# BlueSMiRF-ChipAnt.net
KiCad netlist of a schematic drawn in EAGLE
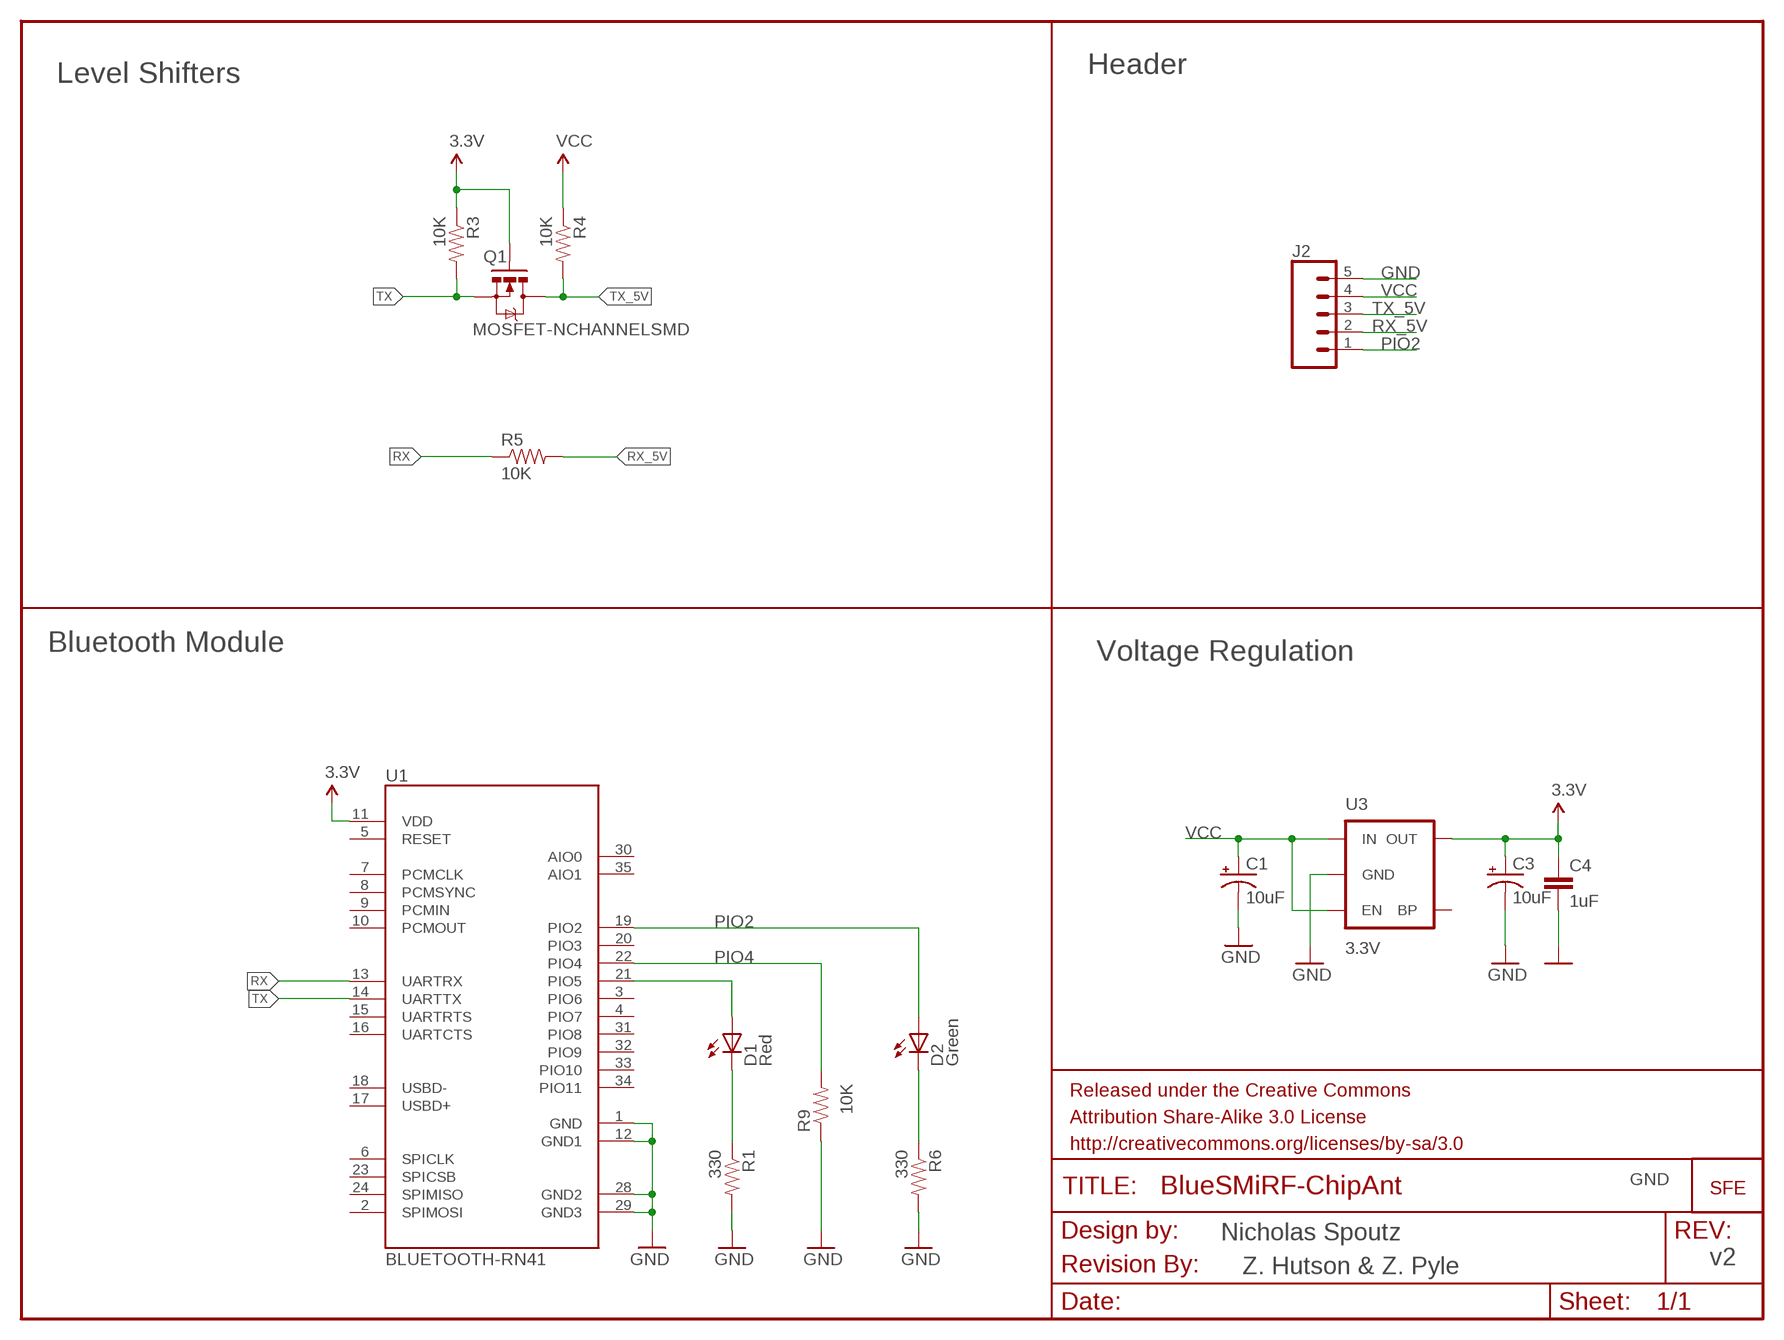
[diagram p0: schematic, sheet 1]

(export (version "E")
  (design (tool "Eeschema 10.0.6"))
  (components
    (comp (ref "C1")
      (value "10uF")
      (footprint "eagle-import:EIA3216")
      (libsource (lib "eagle-import") (part "CAP_POL1206"))
    )
    (comp (ref "C3")
      (value "10uF")
      (footprint "eagle-import:EIA3216")
      (libsource (lib "eagle-import") (part "CAP_POL1206"))
    )
    (comp (ref "C4")
      (value "1uF")
      (footprint "eagle-import:0603-CAP")
      (libsource (lib "eagle-import") (part "CAP0603-CAP"))
    )
    (comp (ref "D1")
      (value "Red")
      (footprint "eagle-import:LED-0603")
      (libsource (lib "eagle-import") (part "LED0603"))
    )
    (comp (ref "D2")
      (value "Green")
      (footprint "eagle-import:LED-0603")
      (libsource (lib "eagle-import") (part "LED0603"))
    )
    (comp (ref "FRAME1")
      (value "FRAME-LETTER")
      (footprint "eagle-import:CREATIVE_COMMONS")
      (libsource (lib "eagle-import") (part "FRAME-LETTER"))
    )
    (comp (ref "J2")
      (value "CONN_05JST")
      (footprint "eagle-import:JST-5-PTH")
      (libsource (lib "eagle-import") (part "CONN_05JST"))
    )
    (comp (ref "Q1")
      (value "MOSFET-NCHANNELSMD")
      (footprint "eagle-import:SOT23-3")
      (libsource (lib "eagle-import") (part "MOSFET-NCHANNELSMD"))
    )
    (comp (ref "R1")
      (value "330")
      (footprint "eagle-import:0603-RES")
      (libsource (lib "eagle-import") (part "RESISTOR0603-RES"))
    )
    (comp (ref "R3")
      (value "10K")
      (footprint "eagle-import:0603-RES")
      (libsource (lib "eagle-import") (part "RESISTOR0603-RES"))
    )
    (comp (ref "R4")
      (value "10K")
      (footprint "eagle-import:0603-RES")
      (libsource (lib "eagle-import") (part "RESISTOR0603-RES"))
    )
    (comp (ref "R5")
      (value "10K")
      (footprint "eagle-import:0603-RES")
      (libsource (lib "eagle-import") (part "RESISTOR0603-RES"))
    )
    (comp (ref "R6")
      (value "330")
      (footprint "eagle-import:0603-RES")
      (libsource (lib "eagle-import") (part "RESISTOR0603-RES"))
    )
    (comp (ref "R9")
      (value "10K")
      (footprint "eagle-import:0603-RES")
      (libsource (lib "eagle-import") (part "RESISTOR0603-RES"))
    )
    (comp (ref "U$1")
      (value "LOGO-SFENEW")
      (footprint "eagle-import:SFE-NEW-WEBLOGO")
      (libsource (lib "eagle-import") (part "LOGO-SFENEW"))
    )
    (comp (ref "U$2")
      (value "REVISION")
      (footprint "eagle-import:REVISION")
      (libsource (lib "eagle-import") (part "REVISION"))
    )
    (comp (ref "U1")
      (value "BLUETOOTH-RN41")
      (footprint "eagle-import:RN41")
      (libsource (lib "eagle-import") (part "BLUETOOTH-RN41{dblquote}"))
    )
    (comp (ref "U3")
      (value "3.3V")
      (footprint "eagle-import:SOT23-5")
      (libsource (lib "eagle-import") (part "V_REG_LDOSMD"))
    )
  )
  (nets
    (net (code "1") (name "/PIO2") (class "Default")
      (node (ref "D2") (pin "A") (pinfunction "A_A") (pintype "passive"))
      (node (ref "J2") (pin "1") (pinfunction "1_1") (pintype "passive"))
      (node (ref "U1") (pin "19") (pinfunction "PIO2_19") (pintype "bidirectional"))
    )
    (net (code "2") (name "/PIO4") (class "Default")
      (node (ref "R9") (pin "2") (pinfunction "2_2") (pintype "passive"))
      (node (ref "U1") (pin "22") (pinfunction "PIO4_22") (pintype "bidirectional"))
    )
    (net (code "3") (name "3.3V") (class "Default")
      (node (ref "C3") (pin "A") (pinfunction "+_A") (pintype "passive"))
      (node (ref "C4") (pin "1") (pinfunction "1_1") (pintype "passive"))
      (node (ref "Q1") (pin "1") (pinfunction "G_1") (pintype "passive"))
      (node (ref "R3") (pin "1") (pinfunction "1_1") (pintype "passive"))
      (node (ref "U1") (pin "11") (pinfunction "VDD_11") (pintype "bidirectional"))
      (node (ref "U3") (pin "5") (pinfunction "OUT_5") (pintype "passive"))
    )
    (net (code "4") (name "GND") (class "Default")
      (node (ref "C1") (pin "C") (pinfunction "-_C") (pintype "passive"))
      (node (ref "C3") (pin "C") (pinfunction "-_C") (pintype "passive"))
      (node (ref "C4") (pin "2") (pinfunction "2_2") (pintype "passive"))
      (node (ref "J2") (pin "5") (pinfunction "5_5") (pintype "passive"))
      (node (ref "R1") (pin "2") (pinfunction "2_2") (pintype "passive"))
      (node (ref "R6") (pin "2") (pinfunction "2_2") (pintype "passive"))
      (node (ref "R9") (pin "1") (pinfunction "1_1") (pintype "passive"))
      (node (ref "U1") (pin "1") (pinfunction "GND_1") (pintype "bidirectional"))
      (node (ref "U1") (pin "12") (pinfunction "GND1_12") (pintype "bidirectional"))
      (node (ref "U1") (pin "28") (pinfunction "GND2_28") (pintype "bidirectional"))
      (node (ref "U1") (pin "29") (pinfunction "GND3_29") (pintype "bidirectional"))
      (node (ref "U3") (pin "2") (pinfunction "GND_2") (pintype "input"))
    )
    (net (code "5") (name "Net-(D1-PadC)") (class "Default")
      (node (ref "D1") (pin "C") (pinfunction "C_C") (pintype "passive"))
      (node (ref "R1") (pin "1") (pinfunction "1_1") (pintype "passive"))
    )
    (net (code "6") (name "Net-(D2-PadC)") (class "Default")
      (node (ref "D2") (pin "C") (pinfunction "C_C") (pintype "passive"))
      (node (ref "R6") (pin "1") (pinfunction "1_1") (pintype "passive"))
    )
    (net (code "7") (name "Net-(U1-PIO5)") (class "Default")
      (node (ref "D1") (pin "A") (pinfunction "A_A") (pintype "passive"))
      (node (ref "U1") (pin "21") (pinfunction "PIO5_21") (pintype "bidirectional"))
    )
    (net (code "8") (name "RX") (class "Default")
      (node (ref "R5") (pin "1") (pinfunction "1_1") (pintype "passive"))
      (node (ref "U1") (pin "13") (pinfunction "UARTRX_13") (pintype "bidirectional"))
    )
    (net (code "9") (name "RX_5V") (class "Default")
      (node (ref "J2") (pin "2") (pinfunction "2_2") (pintype "passive"))
      (node (ref "R5") (pin "2") (pinfunction "2_2") (pintype "passive"))
    )
    (net (code "10") (name "TX") (class "Default")
      (node (ref "Q1") (pin "2") (pinfunction "S_2") (pintype "passive"))
      (node (ref "R3") (pin "2") (pinfunction "2_2") (pintype "passive"))
      (node (ref "U1") (pin "14") (pinfunction "UARTTX_14") (pintype "bidirectional"))
    )
    (net (code "11") (name "TX_5V") (class "Default")
      (node (ref "J2") (pin "3") (pinfunction "3_3") (pintype "passive"))
      (node (ref "Q1") (pin "3") (pinfunction "D_3") (pintype "passive"))
      (node (ref "R4") (pin "2") (pinfunction "2_2") (pintype "passive"))
    )
    (net (code "12") (name "VCC") (class "Default")
      (node (ref "C1") (pin "A") (pinfunction "+_A") (pintype "passive"))
      (node (ref "J2") (pin "4") (pinfunction "4_4") (pintype "passive"))
      (node (ref "R4") (pin "1") (pinfunction "1_1") (pintype "passive"))
      (node (ref "U3") (pin "1") (pinfunction "IN_1") (pintype "input"))
      (node (ref "U3") (pin "3") (pinfunction "EN_3") (pintype "input"))
    )
    (net (code "13") (name "unconnected-(U1-AIO0-Pad30)") (class "Default")
      (node (ref "U1") (pin "30") (pinfunction "AIO0_30") (pintype "bidirectional"))
    )
    (net (code "14") (name "unconnected-(U1-AIO1-Pad35)") (class "Default")
      (node (ref "U1") (pin "35") (pinfunction "AIO1_35") (pintype "bidirectional"))
    )
    (net (code "15") (name "unconnected-(U1-PCMCLK-Pad7)") (class "Default")
      (node (ref "U1") (pin "7") (pinfunction "PCMCLK_7") (pintype "bidirectional"))
    )
    (net (code "16") (name "unconnected-(U1-PCMIN-Pad9)") (class "Default")
      (node (ref "U1") (pin "9") (pinfunction "PCMIN_9") (pintype "bidirectional"))
    )
    (net (code "17") (name "unconnected-(U1-PCMOUT-Pad10)") (class "Default")
      (node (ref "U1") (pin "10") (pinfunction "PCMOUT_10") (pintype "bidirectional"))
    )
    (net (code "18") (name "unconnected-(U1-PCMSYNC-Pad8)") (class "Default")
      (node (ref "U1") (pin "8") (pinfunction "PCMSYNC_8") (pintype "bidirectional"))
    )
    (net (code "19") (name "unconnected-(U1-PIO3-Pad20)") (class "Default")
      (node (ref "U1") (pin "20") (pinfunction "PIO3_20") (pintype "bidirectional"))
    )
    (net (code "20") (name "unconnected-(U1-PIO6-Pad3)") (class "Default")
      (node (ref "U1") (pin "3") (pinfunction "PIO6_3") (pintype "bidirectional"))
    )
    (net (code "21") (name "unconnected-(U1-PIO7-Pad4)") (class "Default")
      (node (ref "U1") (pin "4") (pinfunction "PIO7_4") (pintype "bidirectional"))
    )
    (net (code "22") (name "unconnected-(U1-PIO8-Pad31)") (class "Default")
      (node (ref "U1") (pin "31") (pinfunction "PIO8_31") (pintype "bidirectional"))
    )
    (net (code "23") (name "unconnected-(U1-PIO9-Pad32)") (class "Default")
      (node (ref "U1") (pin "32") (pinfunction "PIO9_32") (pintype "bidirectional"))
    )
    (net (code "24") (name "unconnected-(U1-PIO10-Pad33)") (class "Default")
      (node (ref "U1") (pin "33") (pinfunction "PIO10_33") (pintype "bidirectional"))
    )
    (net (code "25") (name "unconnected-(U1-PIO11-Pad34)") (class "Default")
      (node (ref "U1") (pin "34") (pinfunction "PIO11_34") (pintype "bidirectional"))
    )
    (net (code "26") (name "unconnected-(U1-RESET-Pad5)") (class "Default")
      (node (ref "U1") (pin "5") (pinfunction "RESET_5") (pintype "bidirectional"))
    )
    (net (code "27") (name "unconnected-(U1-SPICLK-Pad6)") (class "Default")
      (node (ref "U1") (pin "6") (pinfunction "SPICLK_6") (pintype "bidirectional"))
    )
    (net (code "28") (name "unconnected-(U1-SPICSB-Pad23)") (class "Default")
      (node (ref "U1") (pin "23") (pinfunction "SPICSB_23") (pintype "bidirectional"))
    )
    (net (code "29") (name "unconnected-(U1-SPIMISO-Pad24)") (class "Default")
      (node (ref "U1") (pin "24") (pinfunction "SPIMISO_24") (pintype "bidirectional"))
    )
    (net (code "30") (name "unconnected-(U1-SPIMOSI-Pad2)") (class "Default")
      (node (ref "U1") (pin "2") (pinfunction "SPIMOSI_2") (pintype "bidirectional"))
    )
    (net (code "31") (name "unconnected-(U1-UARTCTS-Pad16)") (class "Default")
      (node (ref "U1") (pin "16") (pinfunction "UARTCTS_16") (pintype "bidirectional"))
    )
    (net (code "32") (name "unconnected-(U1-UARTRTS-Pad15)") (class "Default")
      (node (ref "U1") (pin "15") (pinfunction "UARTRTS_15") (pintype "bidirectional"))
    )
    (net (code "33") (name "unconnected-(U1-USBD+-Pad17)") (class "Default")
      (node (ref "U1") (pin "17") (pinfunction "USBD+_17") (pintype "bidirectional"))
    )
    (net (code "34") (name "unconnected-(U1-USBD--Pad18)") (class "Default")
      (node (ref "U1") (pin "18") (pinfunction "USBD-_18") (pintype "bidirectional"))
    )
    (net (code "35") (name "unconnected-(U3-BP-Pad4)") (class "Default")
      (node (ref "U3") (pin "4") (pinfunction "BP_4") (pintype "input"))
    )
  )
)
